# kameleon-core.net
KiCad netlist of a schematic drawn in EAGLE
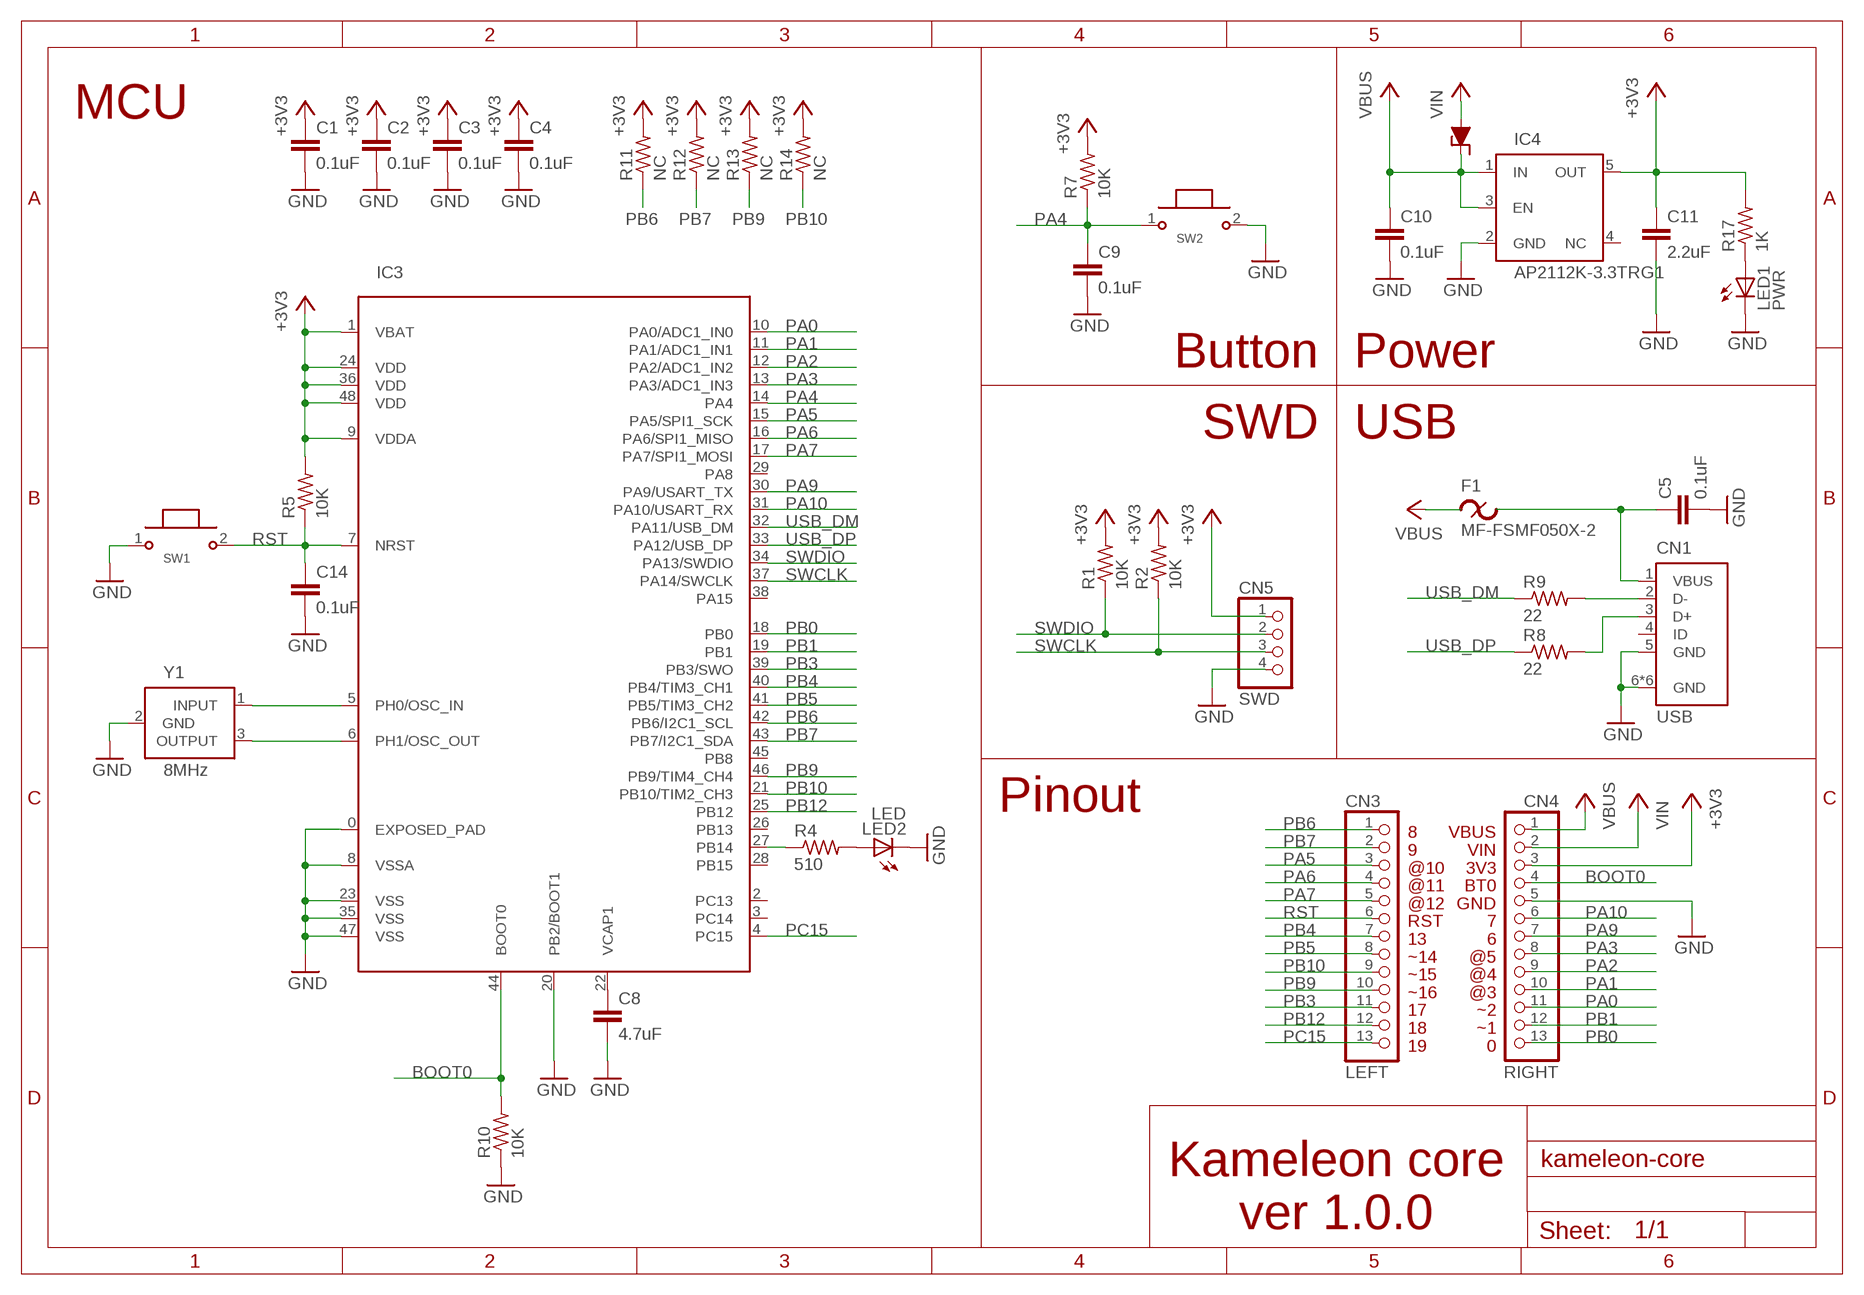
[diagram p0: schematic, sheet 1]

(export (version "E")
  (design (tool "Eeschema 10.0.6"))
  (components
    (comp (ref "C1")
      (value "0.1uF")
      (footprint "eagle-import:1608")
      (libsource (lib "eagle-import") (part "CAP"))
    )
    (comp (ref "C2")
      (value "0.1uF")
      (footprint "eagle-import:1608")
      (libsource (lib "eagle-import") (part "CAP"))
    )
    (comp (ref "C3")
      (value "0.1uF")
      (footprint "eagle-import:1608")
      (libsource (lib "eagle-import") (part "CAP"))
    )
    (comp (ref "C4")
      (value "0.1uF")
      (footprint "eagle-import:1608")
      (libsource (lib "eagle-import") (part "CAP"))
    )
    (comp (ref "C5")
      (value "0.1uF")
      (footprint "eagle-import:1608")
      (libsource (lib "eagle-import") (part "CAP"))
    )
    (comp (ref "C8")
      (value "4.7uF")
      (footprint "eagle-import:2012")
      (libsource (lib "eagle-import") (part "CAPB"))
    )
    (comp (ref "C9")
      (value "0.1uF")
      (footprint "eagle-import:1608")
      (libsource (lib "eagle-import") (part "CAP"))
    )
    (comp (ref "C10")
      (value "0.1uF")
      (footprint "eagle-import:1608")
      (libsource (lib "eagle-import") (part "CAP"))
    )
    (comp (ref "C11")
      (value "2.2uF")
      (footprint "eagle-import:2012")
      (libsource (lib "eagle-import") (part "CAPB"))
    )
    (comp (ref "C14")
      (value "0.1uF")
      (footprint "eagle-import:1608")
      (libsource (lib "eagle-import") (part "CAP"))
    )
    (comp (ref "CN1")
      (value "USB")
      (footprint "eagle-import:1050170001")
      (libsource (lib "eagle-import") (part "1050170001"))
    )
    (comp (ref "CN3")
      (value "LEFT")
      (footprint "eagle-import:1X13")
      (libsource (lib "eagle-import") (part "PINHD-1X13"))
    )
    (comp (ref "CN4")
      (value "RIGHT")
      (footprint "eagle-import:1X13")
      (libsource (lib "eagle-import") (part "PINHD-1X13"))
    )
    (comp (ref "CN5")
      (value "SWD")
      (footprint "eagle-import:1X04")
      (libsource (lib "eagle-import") (part "PINHD-1X4"))
    )
    (comp (ref "D1")
      (value "MBR120VLSF")
      (footprint "eagle-import:SOD-123FL")
      (libsource (lib "eagle-import") (part "MBR120VLSF"))
    )
    (comp (ref "F1")
      (value "MF-FSMF050X-2")
      (footprint "eagle-import:1608")
      (libsource (lib "eagle-import") (part "MF-FSMF050X-2"))
    )
    (comp (ref "IC3")
      (value "STM32F411CE/UFQFPN48")
      (footprint "eagle-import:UFQFPN48")
      (libsource (lib "eagle-import") (part "STM32F411CE/UFQFPN48"))
    )
    (comp (ref "IC4")
      (value "AP2112K-3.3TRG1")
      (footprint "eagle-import:SOT25")
      (libsource (lib "eagle-import") (part "AP2112K-3.3TRG1"))
    )
    (comp (ref "LED1")
      (value "PWR")
      (footprint "eagle-import:D1608")
      (libsource (lib "eagle-import") (part "LED"))
    )
    (comp (ref "LED2")
      (value "LED")
      (footprint "eagle-import:D1608")
      (libsource (lib "eagle-import") (part "LED"))
    )
    (comp (ref "R1")
      (value "10K")
      (footprint "eagle-import:1608")
      (libsource (lib "eagle-import") (part "RES"))
    )
    (comp (ref "R2")
      (value "10K")
      (footprint "eagle-import:1608")
      (libsource (lib "eagle-import") (part "RES"))
    )
    (comp (ref "R4")
      (value "510")
      (footprint "eagle-import:1608")
      (libsource (lib "eagle-import") (part "RES"))
    )
    (comp (ref "R5")
      (value "10K")
      (footprint "eagle-import:1608")
      (libsource (lib "eagle-import") (part "RES"))
    )
    (comp (ref "R7")
      (value "10K")
      (footprint "eagle-import:1608")
      (libsource (lib "eagle-import") (part "RES"))
    )
    (comp (ref "R8")
      (value "22")
      (footprint "eagle-import:1608")
      (libsource (lib "eagle-import") (part "RES"))
    )
    (comp (ref "R9")
      (value "22")
      (footprint "eagle-import:1608")
      (libsource (lib "eagle-import") (part "RES"))
    )
    (comp (ref "R10")
      (value "10K")
      (footprint "eagle-import:1608")
      (libsource (lib "eagle-import") (part "RES"))
    )
    (comp (ref "R11")
      (value "NC")
      (footprint "eagle-import:1608")
      (libsource (lib "eagle-import") (part "RES"))
    )
    (comp (ref "R12")
      (value "NC")
      (footprint "eagle-import:1608")
      (libsource (lib "eagle-import") (part "RES"))
    )
    (comp (ref "R13")
      (value "NC")
      (footprint "eagle-import:1608")
      (libsource (lib "eagle-import") (part "RES"))
    )
    (comp (ref "R14")
      (value "NC")
      (footprint "eagle-import:1608")
      (libsource (lib "eagle-import") (part "RES"))
    )
    (comp (ref "R17")
      (value "1K")
      (footprint "eagle-import:1608")
      (libsource (lib "eagle-import") (part "RES"))
    )
    (comp (ref "SW1")
      (value "NRST")
      (footprint "eagle-import:NW3-A03-05")
      (libsource (lib "eagle-import") (part "NW3-A03-05"))
    )
    (comp (ref "SW2")
      (value "BTN")
      (footprint "eagle-import:NW3-A03-05")
      (libsource (lib "eagle-import") (part "NW3-A03-05"))
    )
    (comp (ref "Y1")
      (value "8MHz")
      (footprint "eagle-import:R0")
      (libsource (lib "eagle-import") (part "CSTCE8M00G55Z-R0"))
    )
  )
  (nets
    (net (code "1") (name "+3V3") (class "Default")
      (node (ref "C1") (pin "1") (pinfunction "1_1") (pintype "passive"))
      (node (ref "C11") (pin "1") (pinfunction "1_1") (pintype "passive"))
      (node (ref "C2") (pin "1") (pinfunction "1_1") (pintype "passive"))
      (node (ref "C3") (pin "1") (pinfunction "1_1") (pintype "passive"))
      (node (ref "C4") (pin "1") (pinfunction "1_1") (pintype "passive"))
      (node (ref "CN4") (pin "3") (pinfunction "3_3") (pintype "passive"))
      (node (ref "CN5") (pin "1") (pinfunction "1_1") (pintype "passive"))
      (node (ref "IC3") (pin "1") (pinfunction "VBAT_1") (pintype "power_in"))
      (node (ref "IC3") (pin "24") (pinfunction "VDD_24") (pintype "power_in"))
      (node (ref "IC3") (pin "36") (pinfunction "VDD_36") (pintype "power_in"))
      (node (ref "IC3") (pin "48") (pinfunction "VDD_48") (pintype "power_in"))
      (node (ref "IC3") (pin "9") (pinfunction "VDDA_9") (pintype "power_in"))
      (node (ref "IC4") (pin "5") (pinfunction "OUT_5") (pintype "power_in"))
      (node (ref "R1") (pin "2") (pinfunction "2_2") (pintype "passive"))
      (node (ref "R11") (pin "2") (pinfunction "2_2") (pintype "passive"))
      (node (ref "R12") (pin "2") (pinfunction "2_2") (pintype "passive"))
      (node (ref "R13") (pin "2") (pinfunction "2_2") (pintype "passive"))
      (node (ref "R14") (pin "2") (pinfunction "2_2") (pintype "passive"))
      (node (ref "R17") (pin "2") (pinfunction "2_2") (pintype "passive"))
      (node (ref "R2") (pin "2") (pinfunction "2_2") (pintype "passive"))
      (node (ref "R5") (pin "2") (pinfunction "2_2") (pintype "passive"))
      (node (ref "R7") (pin "2") (pinfunction "2_2") (pintype "passive"))
    )
    (net (code "2") (name "/BOOT0") (class "Default")
      (node (ref "CN4") (pin "4") (pinfunction "4_4") (pintype "passive"))
      (node (ref "IC3") (pin "44") (pinfunction "BOOT0_44") (pintype "bidirectional"))
      (node (ref "R10") (pin "2") (pinfunction "2_2") (pintype "passive"))
    )
    (net (code "3") (name "/PA0") (class "Default")
      (node (ref "CN4") (pin "11") (pinfunction "11_11") (pintype "passive"))
      (node (ref "IC3") (pin "10") (pinfunction "PA0/ADC1_IN0_10") (pintype "bidirectional"))
    )
    (net (code "4") (name "/PA1") (class "Default")
      (node (ref "CN4") (pin "10") (pinfunction "10_10") (pintype "passive"))
      (node (ref "IC3") (pin "11") (pinfunction "PA1/ADC1_IN1_11") (pintype "bidirectional"))
    )
    (net (code "5") (name "/PA2") (class "Default")
      (node (ref "CN4") (pin "9") (pinfunction "9_9") (pintype "passive"))
      (node (ref "IC3") (pin "12") (pinfunction "PA2/ADC1_IN2_12") (pintype "bidirectional"))
    )
    (net (code "6") (name "/PA3") (class "Default")
      (node (ref "CN4") (pin "8") (pinfunction "8_8") (pintype "passive"))
      (node (ref "IC3") (pin "13") (pinfunction "PA3/ADC1_IN3_13") (pintype "bidirectional"))
    )
    (net (code "7") (name "/PA4") (class "Default")
      (node (ref "C9") (pin "1") (pinfunction "1_1") (pintype "passive"))
      (node (ref "IC3") (pin "14") (pinfunction "PA4_14") (pintype "bidirectional"))
      (node (ref "R7") (pin "1") (pinfunction "1_1") (pintype "passive"))
      (node (ref "SW2") (pin "1") (pinfunction "1_1") (pintype "passive"))
    )
    (net (code "8") (name "/PA5") (class "Default")
      (node (ref "CN3") (pin "3") (pinfunction "3_3") (pintype "passive"))
      (node (ref "IC3") (pin "15") (pinfunction "PA5/SPI1_SCK_15") (pintype "bidirectional"))
    )
    (net (code "9") (name "/PA6") (class "Default")
      (node (ref "CN3") (pin "4") (pinfunction "4_4") (pintype "passive"))
      (node (ref "IC3") (pin "16") (pinfunction "PA6/SPI1_MISO_16") (pintype "bidirectional"))
    )
    (net (code "10") (name "/PA7") (class "Default")
      (node (ref "CN3") (pin "5") (pinfunction "5_5") (pintype "passive"))
      (node (ref "IC3") (pin "17") (pinfunction "PA7/SPI1_MOSI_17") (pintype "bidirectional"))
    )
    (net (code "11") (name "/PA9") (class "Default")
      (node (ref "CN4") (pin "7") (pinfunction "7_7") (pintype "passive"))
      (node (ref "IC3") (pin "30") (pinfunction "PA9/USART_TX_30") (pintype "bidirectional"))
    )
    (net (code "12") (name "/PA10") (class "Default")
      (node (ref "CN4") (pin "6") (pinfunction "6_6") (pintype "passive"))
      (node (ref "IC3") (pin "31") (pinfunction "PA10/USART_RX_31") (pintype "bidirectional"))
    )
    (net (code "13") (name "/PB0") (class "Default")
      (node (ref "CN4") (pin "13") (pinfunction "13_13") (pintype "passive"))
      (node (ref "IC3") (pin "18") (pinfunction "PB0_18") (pintype "bidirectional"))
    )
    (net (code "14") (name "/PB1") (class "Default")
      (node (ref "CN4") (pin "12") (pinfunction "12_12") (pintype "passive"))
      (node (ref "IC3") (pin "19") (pinfunction "PB1_19") (pintype "bidirectional"))
    )
    (net (code "15") (name "/PB3") (class "Default")
      (node (ref "CN3") (pin "11") (pinfunction "11_11") (pintype "passive"))
      (node (ref "IC3") (pin "39") (pinfunction "PB3/SWO_39") (pintype "bidirectional"))
    )
    (net (code "16") (name "/PB4") (class "Default")
      (node (ref "CN3") (pin "7") (pinfunction "7_7") (pintype "passive"))
      (node (ref "IC3") (pin "40") (pinfunction "PB4/TIM3_CH1_40") (pintype "bidirectional"))
    )
    (net (code "17") (name "/PB5") (class "Default")
      (node (ref "CN3") (pin "8") (pinfunction "8_8") (pintype "passive"))
      (node (ref "IC3") (pin "41") (pinfunction "PB5/TIM3_CH2_41") (pintype "bidirectional"))
    )
    (net (code "18") (name "/PB6") (class "Default")
      (node (ref "CN3") (pin "1") (pinfunction "1_1") (pintype "passive"))
      (node (ref "IC3") (pin "42") (pinfunction "PB6/I2C1_SCL_42") (pintype "bidirectional"))
      (node (ref "R11") (pin "1") (pinfunction "1_1") (pintype "passive"))
    )
    (net (code "19") (name "/PB7") (class "Default")
      (node (ref "CN3") (pin "2") (pinfunction "2_2") (pintype "passive"))
      (node (ref "IC3") (pin "43") (pinfunction "PB7/I2C1_SDA_43") (pintype "bidirectional"))
      (node (ref "R12") (pin "1") (pinfunction "1_1") (pintype "passive"))
    )
    (net (code "20") (name "/PB9") (class "Default")
      (node (ref "CN3") (pin "10") (pinfunction "10_10") (pintype "passive"))
      (node (ref "IC3") (pin "46") (pinfunction "PB9/TIM4_CH4_46") (pintype "bidirectional"))
      (node (ref "R13") (pin "1") (pinfunction "1_1") (pintype "passive"))
    )
    (net (code "21") (name "/PB10") (class "Default")
      (node (ref "CN3") (pin "9") (pinfunction "9_9") (pintype "passive"))
      (node (ref "IC3") (pin "21") (pinfunction "PB10/TIM2_CH3_21") (pintype "bidirectional"))
      (node (ref "R14") (pin "1") (pinfunction "1_1") (pintype "passive"))
    )
    (net (code "22") (name "/PB12") (class "Default")
      (node (ref "CN3") (pin "12") (pinfunction "12_12") (pintype "passive"))
      (node (ref "IC3") (pin "25") (pinfunction "PB12_25") (pintype "bidirectional"))
    )
    (net (code "23") (name "/PC15") (class "Default")
      (node (ref "CN3") (pin "13") (pinfunction "13_13") (pintype "passive"))
      (node (ref "IC3") (pin "4") (pinfunction "PC15_4") (pintype "bidirectional"))
    )
    (net (code "24") (name "/RST") (class "Default")
      (node (ref "C14") (pin "1") (pinfunction "1_1") (pintype "passive"))
      (node (ref "CN3") (pin "6") (pinfunction "6_6") (pintype "passive"))
      (node (ref "IC3") (pin "7") (pinfunction "NRST_7") (pintype "input"))
      (node (ref "R5") (pin "1") (pinfunction "1_1") (pintype "passive"))
      (node (ref "SW1") (pin "2") (pinfunction "2_2") (pintype "passive"))
    )
    (net (code "25") (name "/SWCLK") (class "Default")
      (node (ref "CN5") (pin "3") (pinfunction "3_3") (pintype "passive"))
      (node (ref "IC3") (pin "37") (pinfunction "PA14/SWCLK_37") (pintype "bidirectional"))
      (node (ref "R2") (pin "1") (pinfunction "1_1") (pintype "passive"))
    )
    (net (code "26") (name "/SWDIO") (class "Default")
      (node (ref "CN5") (pin "2") (pinfunction "2_2") (pintype "passive"))
      (node (ref "IC3") (pin "34") (pinfunction "PA13/SWDIO_34") (pintype "bidirectional"))
      (node (ref "R1") (pin "1") (pinfunction "1_1") (pintype "passive"))
    )
    (net (code "27") (name "/USB_DM") (class "Default")
      (node (ref "IC3") (pin "32") (pinfunction "PA11/USB_DM_32") (pintype "bidirectional"))
      (node (ref "R9") (pin "1") (pinfunction "1_1") (pintype "passive"))
    )
    (net (code "28") (name "/USB_DP") (class "Default")
      (node (ref "IC3") (pin "33") (pinfunction "PA12/USB_DP_33") (pintype "bidirectional"))
      (node (ref "R8") (pin "1") (pinfunction "1_1") (pintype "passive"))
    )
    (net (code "29") (name "GND") (class "Default")
      (node (ref "C1") (pin "2") (pinfunction "2_2") (pintype "passive"))
      (node (ref "C10") (pin "2") (pinfunction "2_2") (pintype "passive"))
      (node (ref "C11") (pin "2") (pinfunction "2_2") (pintype "passive"))
      (node (ref "C14") (pin "2") (pinfunction "2_2") (pintype "passive"))
      (node (ref "C2") (pin "2") (pinfunction "2_2") (pintype "passive"))
      (node (ref "C3") (pin "2") (pinfunction "2_2") (pintype "passive"))
      (node (ref "C4") (pin "2") (pinfunction "2_2") (pintype "passive"))
      (node (ref "C5") (pin "2") (pinfunction "2_2") (pintype "passive"))
      (node (ref "C8") (pin "2") (pinfunction "2_2") (pintype "passive"))
      (node (ref "C9") (pin "2") (pinfunction "2_2") (pintype "passive"))
      (node (ref "CN1") (pin "10") (pinfunction "GND_10") (pintype "passive"))
      (node (ref "CN1") (pin "11") (pinfunction "GND_11") (pintype "passive"))
      (node (ref "CN1") (pin "5") (pinfunction "GND_5") (pintype "passive"))
      (node (ref "CN1") (pin "6") (pinfunction "GND_6") (pintype "passive"))
      (node (ref "CN1") (pin "7") (pinfunction "GND_7") (pintype "passive"))
      (node (ref "CN1") (pin "8") (pinfunction "GND_8") (pintype "passive"))
      (node (ref "CN1") (pin "9") (pinfunction "GND_9") (pintype "passive"))
      (node (ref "CN4") (pin "5") (pinfunction "5_5") (pintype "passive"))
      (node (ref "CN5") (pin "4") (pinfunction "4_4") (pintype "passive"))
      (node (ref "IC3") (pin "0") (pinfunction "EXPOSED_PAD_0") (pintype "passive"))
      (node (ref "IC3") (pin "20") (pinfunction "PB2/BOOT1_20") (pintype "passive"))
      (node (ref "IC3") (pin "23") (pinfunction "VSS_23") (pintype "power_in"))
      (node (ref "IC3") (pin "35") (pinfunction "VSS_35") (pintype "power_in"))
      (node (ref "IC3") (pin "47") (pinfunction "VSS_47") (pintype "power_in"))
      (node (ref "IC3") (pin "8") (pinfunction "VSSA_8") (pintype "power_in"))
      (node (ref "IC4") (pin "2") (pinfunction "GND_2") (pintype "power_in"))
      (node (ref "LED1") (pin "2") (pinfunction "C_2") (pintype "passive"))
      (node (ref "LED2") (pin "2") (pinfunction "C_2") (pintype "passive"))
      (node (ref "R10") (pin "1") (pinfunction "1_1") (pintype "passive"))
      (node (ref "SW1") (pin "1") (pinfunction "1_1") (pintype "passive"))
      (node (ref "SW2") (pin "2") (pinfunction "2_2") (pintype "passive"))
      (node (ref "Y1") (pin "2") (pinfunction "GND_2") (pintype "power_in"))
    )
    (net (code "30") (name "Net-(CN1-D+)") (class "Default")
      (node (ref "CN1") (pin "3") (pinfunction "D+_3") (pintype "passive"))
      (node (ref "R8") (pin "2") (pinfunction "2_2") (pintype "passive"))
    )
    (net (code "31") (name "Net-(CN1-D-)") (class "Default")
      (node (ref "CN1") (pin "2") (pinfunction "D-_2") (pintype "passive"))
      (node (ref "R9") (pin "2") (pinfunction "2_2") (pintype "passive"))
    )
    (net (code "32") (name "Net-(CN1-VBUS)") (class "Default")
      (node (ref "C5") (pin "1") (pinfunction "1_1") (pintype "passive"))
      (node (ref "CN1") (pin "1") (pinfunction "VBUS_1") (pintype "passive"))
      (node (ref "F1") (pin "2") (pinfunction "2_2") (pintype "passive"))
    )
    (net (code "33") (name "Net-(IC3-PB14)") (class "Default")
      (node (ref "IC3") (pin "27") (pinfunction "PB14_27") (pintype "bidirectional"))
      (node (ref "R4") (pin "1") (pinfunction "1_1") (pintype "passive"))
    )
    (net (code "34") (name "Net-(IC3-PH0{slash}OSC_IN)") (class "Default")
      (node (ref "IC3") (pin "5") (pinfunction "PH0/OSC_IN_5") (pintype "bidirectional"))
      (node (ref "Y1") (pin "1") (pinfunction "INPUT_1") (pintype "input"))
    )
    (net (code "35") (name "Net-(IC3-PH1{slash}OSC_OUT)") (class "Default")
      (node (ref "IC3") (pin "6") (pinfunction "PH1/OSC_OUT_6") (pintype "bidirectional"))
      (node (ref "Y1") (pin "3") (pinfunction "OUTPUT_3") (pintype "output"))
    )
    (net (code "36") (name "Net-(IC3-VCAP1)") (class "Default")
      (node (ref "C8") (pin "1") (pinfunction "1_1") (pintype "passive"))
      (node (ref "IC3") (pin "22") (pinfunction "VCAP1_22") (pintype "passive"))
    )
    (net (code "37") (name "Net-(LED1-A)") (class "Default")
      (node (ref "LED1") (pin "1") (pinfunction "A_1") (pintype "passive"))
      (node (ref "R17") (pin "1") (pinfunction "1_1") (pintype "passive"))
    )
    (net (code "38") (name "Net-(LED2-A)") (class "Default")
      (node (ref "LED2") (pin "1") (pinfunction "A_1") (pintype "passive"))
      (node (ref "R4") (pin "2") (pinfunction "2_2") (pintype "passive"))
    )
    (net (code "39") (name "VBUS") (class "Default")
      (node (ref "C10") (pin "1") (pinfunction "1_1") (pintype "passive"))
      (node (ref "CN4") (pin "1") (pinfunction "1_1") (pintype "passive"))
      (node (ref "D1") (pin "2") (pinfunction "2_2") (pintype "passive"))
      (node (ref "F1") (pin "1") (pinfunction "1_1") (pintype "passive"))
      (node (ref "IC4") (pin "1") (pinfunction "IN_1") (pintype "power_in"))
      (node (ref "IC4") (pin "3") (pinfunction "EN_3") (pintype "input"))
    )
    (net (code "40") (name "VIN") (class "Default")
      (node (ref "CN4") (pin "2") (pinfunction "2_2") (pintype "passive"))
      (node (ref "D1") (pin "1") (pinfunction "1_1") (pintype "passive"))
    )
    (net (code "41") (name "unconnected-(CN1-ID-Pad4)") (class "Default")
      (node (ref "CN1") (pin "4") (pinfunction "ID_4") (pintype "passive"))
    )
    (net (code "42") (name "unconnected-(IC3-PA8-Pad29)") (class "Default")
      (node (ref "IC3") (pin "29") (pinfunction "PA8_29") (pintype "bidirectional"))
    )
    (net (code "43") (name "unconnected-(IC3-PA15-Pad38)") (class "Default")
      (node (ref "IC3") (pin "38") (pinfunction "PA15_38") (pintype "bidirectional"))
    )
    (net (code "44") (name "unconnected-(IC3-PB8-Pad45)") (class "Default")
      (node (ref "IC3") (pin "45") (pinfunction "PB8_45") (pintype "bidirectional"))
    )
    (net (code "45") (name "unconnected-(IC3-PB13-Pad26)") (class "Default")
      (node (ref "IC3") (pin "26") (pinfunction "PB13_26") (pintype "bidirectional"))
    )
    (net (code "46") (name "unconnected-(IC3-PB15-Pad28)") (class "Default")
      (node (ref "IC3") (pin "28") (pinfunction "PB15_28") (pintype "bidirectional"))
    )
    (net (code "47") (name "unconnected-(IC3-PC13-Pad2)") (class "Default")
      (node (ref "IC3") (pin "2") (pinfunction "PC13_2") (pintype "bidirectional"))
    )
    (net (code "48") (name "unconnected-(IC3-PC14-Pad3)") (class "Default")
      (node (ref "IC3") (pin "3") (pinfunction "PC14_3") (pintype "bidirectional"))
    )
    (net (code "49") (name "unconnected-(IC4-NC-Pad4)") (class "Default")
      (node (ref "IC4") (pin "4") (pinfunction "NC_4") (pintype "no_connect"))
    )
  )
)
